# Shield_Eth06-REV3.net
KiCad netlist of a schematic drawn in EAGLE
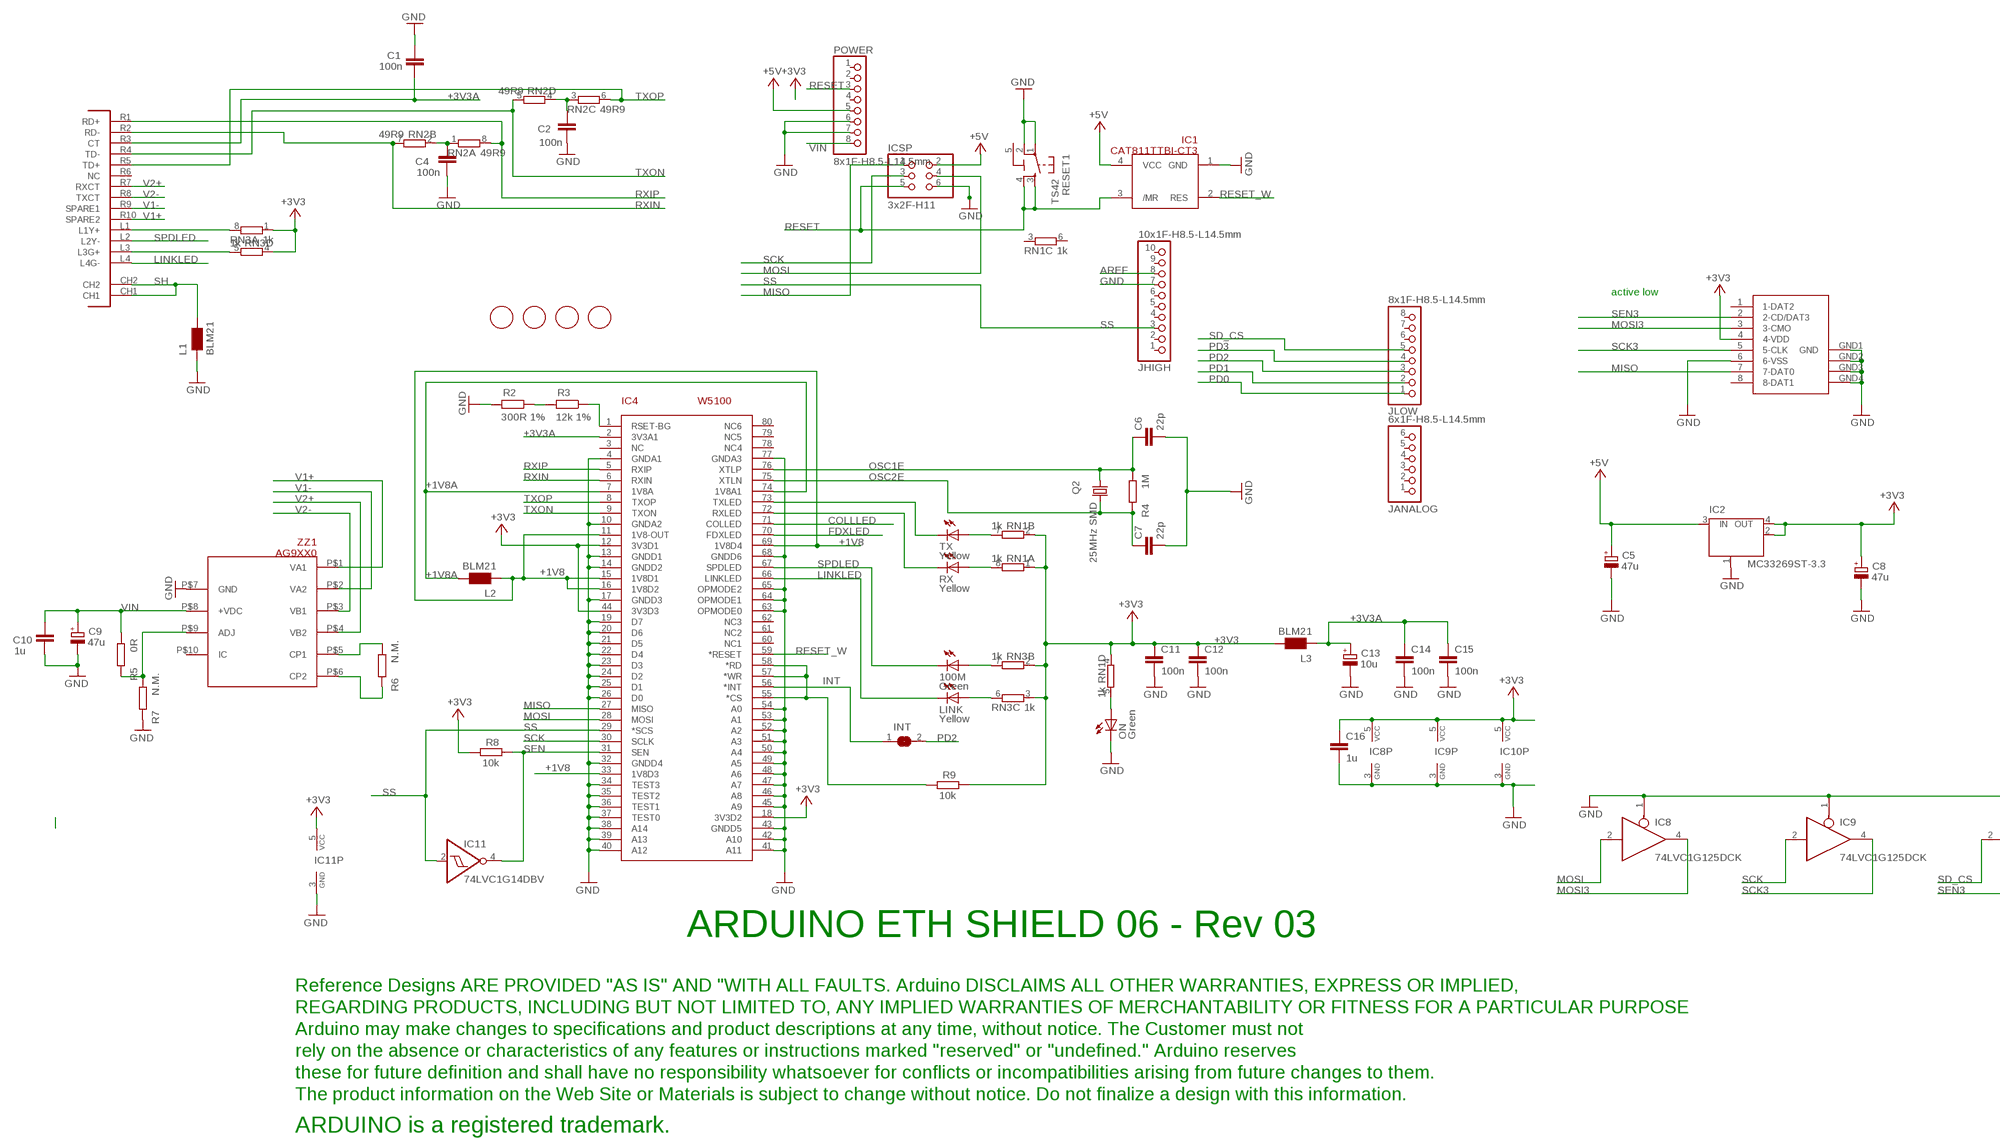
[diagram p0: schematic, sheet 1, part 1 of 2]
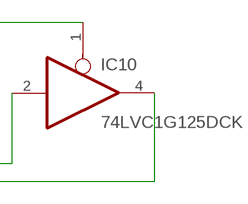
[diagram p1: schematic, sheet 1, part 2 of 2]

(export (version "E")
  (design (tool "Eeschema 10.0.6"))
  (components
    (comp (ref "100M")
      (value "Green")
      (footprint "eagle-import:CHIPLED_0805")
      (libsource (lib "eagle-import") (part "LEDCHIPLED_0805"))
    )
    (comp (ref "C1")
      (value "100n")
      (footprint "eagle-import:C0603-ROUND")
      (libsource (lib "eagle-import") (part "C-EUC0603"))
    )
    (comp (ref "C2")
      (value "100n")
      (footprint "eagle-import:C0603-ROUND")
      (libsource (lib "eagle-import") (part "C-EUC0603"))
    )
    (comp (ref "C4")
      (value "100n")
      (footprint "eagle-import:C0603-ROUND")
      (libsource (lib "eagle-import") (part "C-EUC0603"))
    )
    (comp (ref "C5")
      (value "47u")
      (footprint "eagle-import:PANASONIC_D")
      (libsource (lib "eagle-import") (part "CPOL-EUD"))
    )
    (comp (ref "C6")
      (value "22p")
      (footprint "eagle-import:C0603-ROUND")
      (libsource (lib "eagle-import") (part "C-EUC0603"))
    )
    (comp (ref "C7")
      (value "22p")
      (footprint "eagle-import:C0603-ROUND")
      (libsource (lib "eagle-import") (part "C-EUC0603"))
    )
    (comp (ref "C8")
      (value "47u")
      (footprint "eagle-import:PANASONIC_D")
      (libsource (lib "eagle-import") (part "CPOL-EUD"))
    )
    (comp (ref "C9")
      (value "47u")
      (footprint "eagle-import:PANASONIC_D")
      (libsource (lib "eagle-import") (part "CPOL-EUD"))
    )
    (comp (ref "C10")
      (value "1u")
      (footprint "eagle-import:C0603-ROUND")
      (libsource (lib "eagle-import") (part "C-EUC0603"))
    )
    (comp (ref "C11")
      (value "100n")
      (footprint "eagle-import:C0603-ROUND")
      (libsource (lib "eagle-import") (part "C-EUC0603"))
    )
    (comp (ref "C12")
      (value "100n")
      (footprint "eagle-import:C0603-ROUND")
      (libsource (lib "eagle-import") (part "C-EUC0603"))
    )
    (comp (ref "C13")
      (value "10u")
      (footprint "eagle-import:SMC_B")
      (libsource (lib "eagle-import") (part "CPOL-EUSMCB"))
    )
    (comp (ref "C14")
      (value "100n")
      (footprint "eagle-import:C0603-ROUND")
      (libsource (lib "eagle-import") (part "C-EUC0603"))
    )
    (comp (ref "C15")
      (value "100n")
      (footprint "eagle-import:C0603-ROUND")
      (libsource (lib "eagle-import") (part "C-EUC0603"))
    )
    (comp (ref "C16")
      (value "1u")
      (footprint "eagle-import:C0603-ROUND")
      (libsource (lib "eagle-import") (part "C-EUC0603"))
    )
    (comp (ref "FID1")
      (value "FIDUCIALMOUNT")
      (footprint "eagle-import:FIDUCIA-MOUNT")
      (libsource (lib "eagle-import") (part "FIDUCIALMOUNT"))
    )
    (comp (ref "FID2")
      (value "FIDUCIALMOUNT")
      (footprint "eagle-import:FIDUCIA-MOUNT")
      (libsource (lib "eagle-import") (part "FIDUCIALMOUNT"))
    )
    (comp (ref "FID3")
      (value "FIDUCIALMOUNT")
      (footprint "eagle-import:FIDUCIA-MOUNT")
      (libsource (lib "eagle-import") (part "FIDUCIALMOUNT"))
    )
    (comp (ref "FID4")
      (value "FIDUCIALMOUNT")
      (footprint "eagle-import:FIDUCIA-MOUNT")
      (libsource (lib "eagle-import") (part "FIDUCIALMOUNT"))
    )
    (comp (ref "IC1")
      (value "CAT811TTBI-CT3")
      (footprint "eagle-import:SOT143")
      (libsource (lib "eagle-import") (part "STM812"))
    )
    (comp (ref "IC2")
      (value "MC33269ST-3.3")
      (footprint "eagle-import:SOT223")
      (libsource (lib "eagle-import") (part "MC33269ST-3.3T3"))
    )
    (comp (ref "IC4")
      (value "W5100")
      (footprint "eagle-import:SQFP-S-10X10-80")
      (libsource (lib "eagle-import") (part "W5100"))
    )
    (comp (ref "IC8")
      (value "74LVC1G125DCK")
      (footprint "eagle-import:SC70-5")
      (libsource (lib "eagle-import") (part "741G125DCKLVC"))
    )
    (comp (ref "IC9")
      (value "74LVC1G125DCK")
      (footprint "eagle-import:SC70-5")
      (libsource (lib "eagle-import") (part "741G125DCKLVC"))
    )
    (comp (ref "IC10")
      (value "74LVC1G125DCK")
      (footprint "eagle-import:SC70-5")
      (libsource (lib "eagle-import") (part "741G125DCKLVC"))
    )
    (comp (ref "IC11")
      (value "74LVC1G14DBV")
      (footprint "eagle-import:SOT23-5")
      (libsource (lib "eagle-import") (part "741G14DBVLVC"))
    )
    (comp (ref "ICSP")
      (value "3x2F-H11")
      (footprint "eagle-import:2X03")
      (libsource (lib "eagle-import") (part "PINHD-2X3"))
    )
    (comp (ref "INT") (value "SJ") (footprint "eagle-import:SJ") (libsource (lib "eagle-import") (part "SJ")))
    (comp (ref "JANALOG")
      (value "6x1F-H8.5-L14.5mm")
      (footprint "eagle-import:1X06")
      (libsource (lib "eagle-import") (part "PINHD-1X6"))
    )
    (comp (ref "JHIGH")
      (value "10x1F-H8.5-L14.5mm")
      (footprint "eagle-import:1X10")
      (libsource (lib "eagle-import") (part "PINHD-1X10"))
    )
    (comp (ref "JLOW")
      (value "8x1F-H8.5-L14.5mm")
      (footprint "eagle-import:1X08")
      (libsource (lib "eagle-import") (part "PINHD-1X8"))
    )
    (comp (ref "L1")
      (value "BLM21")
      (footprint "eagle-import:0805")
      (libsource (lib "eagle-import") (part "WE-CBF_0805"))
    )
    (comp (ref "L2")
      (value "BLM21")
      (footprint "eagle-import:0805")
      (libsource (lib "eagle-import") (part "WE-CBF_0805"))
    )
    (comp (ref "L3")
      (value "BLM21")
      (footprint "eagle-import:0805")
      (libsource (lib "eagle-import") (part "WE-CBF_0805"))
    )
    (comp (ref "LINK")
      (value "Yellow")
      (footprint "eagle-import:CHIPLED_0805")
      (libsource (lib "eagle-import") (part "LEDCHIPLED_0805"))
    )
    (comp (ref "ON")
      (value "Green")
      (footprint "eagle-import:CHIPLED_0805")
      (libsource (lib "eagle-import") (part "LEDCHIPLED_0805"))
    )
    (comp (ref "POWER")
      (value "8x1F-H8.5-L14.5mm")
      (footprint "eagle-import:1X08")
      (libsource (lib "eagle-import") (part "PINHD-1X8"))
    )
    (comp (ref "Q2")
      (value "25MHz SMD")
      (footprint "eagle-import:HC49UP")
      (libsource (lib "eagle-import") (part "CRYSTALHC49UP"))
    )
    (comp (ref "R2")
      (value "300R 1%")
      (footprint "eagle-import:R0603-ROUND")
      (libsource (lib "eagle-import") (part "R-EU_0603-RND"))
    )
    (comp (ref "R3")
      (value "12k 1%")
      (footprint "eagle-import:R0603-ROUND")
      (libsource (lib "eagle-import") (part "R-EU_0603-RND"))
    )
    (comp (ref "R4")
      (value "1M")
      (footprint "eagle-import:R0603-ROUND")
      (libsource (lib "eagle-import") (part "R-EU_0603-RND"))
    )
    (comp (ref "R5")
      (value "0R")
      (footprint "eagle-import:R0603-ROUND")
      (libsource (lib "eagle-import") (part "R-EU_0603-RND"))
    )
    (comp (ref "R6")
      (value "N.M.")
      (footprint "eagle-import:R0603-ROUND")
      (libsource (lib "eagle-import") (part "R-EU_0603-RND"))
    )
    (comp (ref "R7")
      (value "N.M.")
      (footprint "eagle-import:R0603-ROUND")
      (libsource (lib "eagle-import") (part "R-EU_0603-RND"))
    )
    (comp (ref "R8")
      (value "10k")
      (footprint "eagle-import:R0603-ROUND")
      (libsource (lib "eagle-import") (part "R-EU_0603-RND"))
    )
    (comp (ref "R9")
      (value "10k")
      (footprint "eagle-import:R0603-ROUND")
      (libsource (lib "eagle-import") (part "R-EU_R0603"))
    )
    (comp (ref "RESET1")
      (value "TS42")
      (footprint "eagle-import:TS42")
      (libsource (lib "eagle-import") (part "TS42"))
    )
    (comp (ref "RN1")
      (value "1k")
      (footprint "eagle-import:CAY16")
      (libsource (lib "eagle-import") (part "4R-NCAY16"))
    )
    (comp (ref "RN2")
      (value "49R9")
      (footprint "eagle-import:CAY16")
      (libsource (lib "eagle-import") (part "4R-NCAY16"))
    )
    (comp (ref "RN3")
      (value "1k")
      (footprint "eagle-import:CAY16")
      (libsource (lib "eagle-import") (part "4R-NCAY16"))
    )
    (comp (ref "RX")
      (value "Yellow")
      (footprint "eagle-import:CHIPLED_0805")
      (libsource (lib "eagle-import") (part "LEDCHIPLED_0805"))
    )
    (comp (ref "TX")
      (value "Yellow")
      (footprint "eagle-import:CHIPLED_0805")
      (libsource (lib "eagle-import") (part "LEDCHIPLED_0805"))
    )
    (comp (ref "U$1")
      (value "POE-RJ45")
      (footprint "eagle-import:POE-RJ45")
      (libsource (lib "eagle-import") (part "POE-RJ45"))
    )
    (comp (ref "U$2")
      (value "DISCLAIMER")
      (footprint "eagle-import:DISCLAIMER")
      (libsource (lib "eagle-import") (part "DISCLAIMER"))
    )
    (comp (ref "X1")
      (value "SDCARD-15TW-8821")
      (footprint "eagle-import:SDCARD-15TW-8821")
      (libsource (lib "eagle-import") (part "SDCARD-15TW-8821"))
    )
    (comp (ref "ZZ1")
      (value "AG9XX0")
      (footprint "eagle-import:AG9000")
      (libsource (lib "eagle-import") (part "AG9XX0"))
    )
  )
  (nets
    (net (code "1") (name "+3V3") (class "Default")
      (node (ref "C11") (pin "1") (pinfunction "1_1") (pintype "passive"))
      (node (ref "C12") (pin "1") (pinfunction "1_1") (pintype "passive"))
      (node (ref "C16") (pin "1") (pinfunction "1_1") (pintype "passive"))
      (node (ref "C8") (pin "+") (pinfunction "+_+") (pintype "passive"))
      (node (ref "IC10") (pin "5") (pinfunction "VCC_5") (pintype "power_in"))
      (node (ref "IC11") (pin "5") (pinfunction "VCC_5") (pintype "power_in"))
      (node (ref "IC2") (pin "2") (pinfunction "OUT_2") (pintype "passive"))
      (node (ref "IC2") (pin "4") (pinfunction "OUT_4") (pintype "passive"))
      (node (ref "IC4") (pin "12") (pinfunction "3V3D1_12") (pintype "power_in"))
      (node (ref "IC4") (pin "18") (pinfunction "3V3D2_18") (pintype "power_in"))
      (node (ref "IC4") (pin "44") (pinfunction "3V3D3_44") (pintype "power_in"))
      (node (ref "IC8") (pin "5") (pinfunction "VCC_5") (pintype "power_in"))
      (node (ref "IC9") (pin "5") (pinfunction "VCC_5") (pintype "power_in"))
      (node (ref "L3") (pin "2") (pinfunction "2_2") (pintype "passive"))
      (node (ref "R8") (pin "1") (pinfunction "1_1") (pintype "passive"))
      (node (ref "R9") (pin "2") (pinfunction "2_2") (pintype "passive"))
      (node (ref "RN1") (pin "1") (pinfunction "1_1") (pintype "passive"))
      (node (ref "RN1") (pin "2") (pinfunction "1_2") (pintype "passive"))
      (node (ref "RN1") (pin "4") (pinfunction "1_4") (pintype "passive"))
      (node (ref "RN3") (pin "1") (pinfunction "1_1") (pintype "passive"))
      (node (ref "RN3") (pin "2") (pinfunction "1_2") (pintype "passive"))
      (node (ref "RN3") (pin "3") (pinfunction "1_3") (pintype "passive"))
      (node (ref "RN3") (pin "4") (pinfunction "1_4") (pintype "passive"))
      (node (ref "X1") (pin "4") (pinfunction "4-VDD_4") (pintype "bidirectional"))
    )
    (net (code "2") (name "+5V") (class "Default")
      (node (ref "C5") (pin "+") (pinfunction "+_+") (pintype "passive"))
      (node (ref "IC1") (pin "4") (pinfunction "VCC_4") (pintype "power_in"))
      (node (ref "IC2") (pin "3") (pinfunction "IN_3") (pintype "input"))
      (node (ref "ICSP") (pin "2") (pinfunction "2_2") (pintype "passive"))
      (node (ref "POWER") (pin "5") (pinfunction "5_5") (pintype "passive"))
    )
    (net (code "3") (name "/+1V8") (class "Default")
      (node (ref "IC4") (pin "11") (pinfunction "1V8-OUT_11") (pintype "power_in"))
      (node (ref "IC4") (pin "15") (pinfunction "1V8D1_15") (pintype "power_in"))
      (node (ref "IC4") (pin "16") (pinfunction "1V8D2_16") (pintype "power_in"))
      (node (ref "IC4") (pin "33") (pinfunction "1V8D3_33") (pintype "power_in"))
      (node (ref "IC4") (pin "69") (pinfunction "1V8D4_69") (pintype "power_in"))
      (node (ref "L2") (pin "1") (pinfunction "1_1") (pintype "passive"))
    )
    (net (code "4") (name "/+1V8A") (class "Default")
      (node (ref "IC4") (pin "7") (pinfunction "1V8A_7") (pintype "power_in"))
      (node (ref "IC4") (pin "74") (pinfunction "1V8A1_74") (pintype "power_in"))
      (node (ref "L2") (pin "2") (pinfunction "2_2") (pintype "passive"))
    )
    (net (code "5") (name "/+3V3A") (class "Default")
      (node (ref "C1") (pin "1") (pinfunction "1_1") (pintype "passive"))
      (node (ref "C13") (pin "+") (pinfunction "+_+") (pintype "passive"))
      (node (ref "C14") (pin "1") (pinfunction "1_1") (pintype "passive"))
      (node (ref "C15") (pin "1") (pinfunction "1_1") (pintype "passive"))
      (node (ref "IC4") (pin "2") (pinfunction "3V3A1_2") (pintype "power_in"))
      (node (ref "L3") (pin "1") (pinfunction "1_1") (pintype "passive"))
      (node (ref "U$1") (pin "R3") (pinfunction "CT_R3") (pintype "bidirectional"))
    )
    (net (code "6") (name "/5-GND") (class "Default")
      (node (ref "RESET1") (pin "5") (pinfunction "5-GND_5") (pintype "power_in"))
    )
    (net (code "7") (name "/AREF") (class "Default")
      (node (ref "JHIGH") (pin "8") (pinfunction "8_8") (pintype "passive"))
    )
    (net (code "8") (name "/COLLLED") (class "Default")
      (node (ref "IC4") (pin "71") (pinfunction "COLLED_71") (pintype "output"))
    )
    (net (code "9") (name "/FDXLED") (class "Default")
      (node (ref "IC4") (pin "70") (pinfunction "FDXLED_70") (pintype "output"))
    )
    (net (code "10") (name "/INT") (class "Default")
      (node (ref "IC4") (pin "56") (pinfunction "*INT_56") (pintype "input"))
      (node (ref "INT") (pin "1") (pinfunction "1_1") (pintype "passive"))
    )
    (net (code "11") (name "/LINKLED") (class "Default")
      (node (ref "IC4") (pin "66") (pinfunction "LINKLED_66") (pintype "output"))
      (node (ref "LINK") (pin "C") (pinfunction "C_C") (pintype "passive"))
      (node (ref "U$1") (pin "L4") (pinfunction "L4G-_L4") (pintype "bidirectional"))
    )
    (net (code "12") (name "/MISO") (class "Default")
      (node (ref "IC4") (pin "27") (pinfunction "MISO_27") (pintype "input"))
      (node (ref "ICSP") (pin "1") (pinfunction "1_1") (pintype "passive"))
      (node (ref "X1") (pin "7") (pinfunction "7-DAT0_7") (pintype "bidirectional"))
    )
    (net (code "13") (name "/MOSI") (class "Default")
      (node (ref "IC4") (pin "28") (pinfunction "MOSI_28") (pintype "output"))
      (node (ref "IC8") (pin "2") (pinfunction "I_2") (pintype "input"))
      (node (ref "ICSP") (pin "4") (pinfunction "4_4") (pintype "passive"))
    )
    (net (code "14") (name "/MOSI3") (class "Default")
      (node (ref "IC8") (pin "4") (pinfunction "O_4") (pintype "tri_state"))
      (node (ref "X1") (pin "3") (pinfunction "3-CMO_3") (pintype "bidirectional"))
    )
    (net (code "15") (name "/OSC1E") (class "Default")
      (node (ref "C6") (pin "1") (pinfunction "1_1") (pintype "passive"))
      (node (ref "IC4") (pin "76") (pinfunction "XTLP_76") (pintype "output"))
      (node (ref "Q2") (pin "1") (pinfunction "1_1") (pintype "passive"))
      (node (ref "R4") (pin "1") (pinfunction "1_1") (pintype "passive"))
    )
    (net (code "16") (name "/OSC2E") (class "Default")
      (node (ref "C7") (pin "1") (pinfunction "1_1") (pintype "passive"))
      (node (ref "IC4") (pin "75") (pinfunction "XTLN_75") (pintype "output"))
      (node (ref "Q2") (pin "2") (pinfunction "2_2") (pintype "passive"))
      (node (ref "R4") (pin "2") (pinfunction "2_2") (pintype "passive"))
    )
    (net (code "17") (name "/PD0") (class "Default")
      (node (ref "JLOW") (pin "1") (pinfunction "1_1") (pintype "passive"))
    )
    (net (code "18") (name "/PD1") (class "Default")
      (node (ref "JLOW") (pin "2") (pinfunction "2_2") (pintype "passive"))
    )
    (net (code "19") (name "/PD2") (class "Default")
      (node (ref "INT") (pin "2") (pinfunction "2_2") (pintype "passive"))
      (node (ref "JLOW") (pin "3") (pinfunction "3_3") (pintype "passive"))
    )
    (net (code "20") (name "/PD3") (class "Default")
      (node (ref "JLOW") (pin "4") (pinfunction "4_4") (pintype "passive"))
    )
    (net (code "21") (name "/RESET") (class "Default")
      (node (ref "IC1") (pin "3") (pinfunction "/MR_3") (pintype "input"))
      (node (ref "ICSP") (pin "5") (pinfunction "5_5") (pintype "passive"))
      (node (ref "POWER") (pin "3") (pinfunction "3_3") (pintype "passive"))
      (node (ref "RESET1") (pin "3") (pinfunction "3_3") (pintype "passive"))
      (node (ref "RESET1") (pin "4") (pinfunction "4_4") (pintype "passive"))
    )
    (net (code "22") (name "/RESET_W") (class "Default")
      (node (ref "IC1") (pin "2") (pinfunction "RES_2") (pintype "output"))
      (node (ref "IC4") (pin "59") (pinfunction "*RESET_59") (pintype "input"))
    )
    (net (code "23") (name "/RXIN") (class "Default")
      (node (ref "IC4") (pin "6") (pinfunction "RXIN_6") (pintype "input"))
      (node (ref "RN2") (pin "7") (pinfunction "2_7") (pintype "passive"))
      (node (ref "U$1") (pin "R2") (pinfunction "RD-_R2") (pintype "bidirectional"))
    )
    (net (code "24") (name "/RXIP") (class "Default")
      (node (ref "IC4") (pin "5") (pinfunction "RXIP_5") (pintype "input"))
      (node (ref "RN2") (pin "8") (pinfunction "2_8") (pintype "passive"))
      (node (ref "U$1") (pin "R1") (pinfunction "RD+_R1") (pintype "bidirectional"))
    )
    (net (code "25") (name "/SCK") (class "Default")
      (node (ref "IC4") (pin "30") (pinfunction "SCLK_30") (pintype "input"))
      (node (ref "IC9") (pin "2") (pinfunction "I_2") (pintype "input"))
      (node (ref "ICSP") (pin "3") (pinfunction "3_3") (pintype "passive"))
    )
    (net (code "26") (name "/SCK3") (class "Default")
      (node (ref "IC9") (pin "4") (pinfunction "O_4") (pintype "tri_state"))
      (node (ref "X1") (pin "5") (pinfunction "5-CLK_5") (pintype "bidirectional"))
    )
    (net (code "27") (name "/SD_CS") (class "Default")
      (node (ref "IC10") (pin "2") (pinfunction "I_2") (pintype "input"))
      (node (ref "JLOW") (pin "5") (pinfunction "5_5") (pintype "passive"))
    )
    (net (code "28") (name "/SEN") (class "Default")
      (node (ref "IC11") (pin "4") (pinfunction "O_4") (pintype "output"))
      (node (ref "IC4") (pin "31") (pinfunction "SEN_31") (pintype "input"))
      (node (ref "R8") (pin "2") (pinfunction "2_2") (pintype "passive"))
    )
    (net (code "29") (name "/SEN3") (class "Default")
      (node (ref "IC10") (pin "4") (pinfunction "O_4") (pintype "tri_state"))
      (node (ref "X1") (pin "2") (pinfunction "2-CD/DAT3_2") (pintype "bidirectional"))
    )
    (net (code "30") (name "/SH") (class "Default")
      (node (ref "L1") (pin "2") (pinfunction "2_2") (pintype "passive"))
      (node (ref "U$1") (pin "CH1") (pinfunction "CH1_CH1") (pintype "bidirectional"))
      (node (ref "U$1") (pin "CH2") (pinfunction "CH2_CH2") (pintype "bidirectional"))
    )
    (net (code "31") (name "/SPDLED") (class "Default")
      (node (ref "100M") (pin "C") (pinfunction "C_C") (pintype "passive"))
      (node (ref "IC4") (pin "67") (pinfunction "SPDLED_67") (pintype "output"))
      (node (ref "U$1") (pin "L2") (pinfunction "L2Y-_L2") (pintype "bidirectional"))
    )
    (net (code "32") (name "/SS") (class "Default")
      (node (ref "IC11") (pin "2") (pinfunction "I_2") (pintype "input"))
      (node (ref "IC4") (pin "29") (pinfunction "*SCS_29") (pintype "input"))
      (node (ref "JHIGH") (pin "3") (pinfunction "3_3") (pintype "passive"))
    )
    (net (code "33") (name "/TXON") (class "Default")
      (node (ref "IC4") (pin "9") (pinfunction "TXON_9") (pintype "output"))
      (node (ref "RN2") (pin "5") (pinfunction "2_5") (pintype "passive"))
      (node (ref "U$1") (pin "R4") (pinfunction "TD-_R4") (pintype "bidirectional"))
    )
    (net (code "34") (name "/TXOP") (class "Default")
      (node (ref "IC4") (pin "8") (pinfunction "TXOP_8") (pintype "output"))
      (node (ref "RN2") (pin "6") (pinfunction "2_6") (pintype "passive"))
      (node (ref "U$1") (pin "R5") (pinfunction "TD+_R5") (pintype "bidirectional"))
    )
    (net (code "35") (name "/V1+") (class "Default")
      (node (ref "U$1") (pin "R10") (pinfunction "SPARE2_R10") (pintype "bidirectional"))
      (node (ref "ZZ1") (pin "P$1") (pinfunction "VA1_P$1") (pintype "input"))
    )
    (net (code "36") (name "/V1-") (class "Default")
      (node (ref "U$1") (pin "R9") (pinfunction "SPARE1_R9") (pintype "bidirectional"))
      (node (ref "ZZ1") (pin "P$2") (pinfunction "VA2_P$2") (pintype "input"))
    )
    (net (code "37") (name "/V2+") (class "Default")
      (node (ref "U$1") (pin "R7") (pinfunction "RXCT_R7") (pintype "bidirectional"))
      (node (ref "ZZ1") (pin "P$4") (pinfunction "VB2_P$4") (pintype "input"))
    )
    (net (code "38") (name "/V2-") (class "Default")
      (node (ref "U$1") (pin "R8") (pinfunction "TXCT_R8") (pintype "bidirectional"))
      (node (ref "ZZ1") (pin "P$3") (pinfunction "VB1_P$3") (pintype "input"))
    )
    (net (code "39") (name "/VIN") (class "Default")
      (node (ref "C10") (pin "2") (pinfunction "2_2") (pintype "passive"))
      (node (ref "C9") (pin "+") (pinfunction "+_+") (pintype "passive"))
      (node (ref "POWER") (pin "8") (pinfunction "8_8") (pintype "passive"))
      (node (ref "R5") (pin "1") (pinfunction "1_1") (pintype "passive"))
      (node (ref "ZZ1") (pin "P$8") (pinfunction "+VDC_P$8") (pintype "power_in"))
    )
    (net (code "40") (name "GND") (class "Default")
      (node (ref "C1") (pin "2") (pinfunction "2_2") (pintype "passive"))
      (node (ref "C10") (pin "1") (pinfunction "1_1") (pintype "passive"))
      (node (ref "C11") (pin "2") (pinfunction "2_2") (pintype "passive"))
      (node (ref "C12") (pin "2") (pinfunction "2_2") (pintype "passive"))
      (node (ref "C13") (pin "-") (pinfunction "-_-") (pintype "passive"))
      (node (ref "C14") (pin "2") (pinfunction "2_2") (pintype "passive"))
      (node (ref "C15") (pin "2") (pinfunction "2_2") (pintype "passive"))
      (node (ref "C16") (pin "2") (pinfunction "2_2") (pintype "passive"))
      (node (ref "C2") (pin "1") (pinfunction "1_1") (pintype "passive"))
      (node (ref "C4") (pin "1") (pinfunction "1_1") (pintype "passive"))
      (node (ref "C5") (pin "-") (pinfunction "-_-") (pintype "passive"))
      (node (ref "C6") (pin "2") (pinfunction "2_2") (pintype "passive"))
      (node (ref "C7") (pin "2") (pinfunction "2_2") (pintype "passive"))
      (node (ref "C8") (pin "-") (pinfunction "-_-") (pintype "passive"))
      (node (ref "C9") (pin "-") (pinfunction "-_-") (pintype "passive"))
      (node (ref "IC1") (pin "1") (pinfunction "GND_1") (pintype "power_in"))
      (node (ref "IC10") (pin "1") (pinfunction "OE_1") (pintype "input"))
      (node (ref "IC10") (pin "3") (pinfunction "GND_3") (pintype "power_in"))
      (node (ref "IC11") (pin "3") (pinfunction "GND_3") (pintype "power_in"))
      (node (ref "IC2") (pin "1") (pinfunction "GND/ADJ_1") (pintype "input"))
      (node (ref "IC4") (pin "10") (pinfunction "GNDA2_10") (pintype "power_in"))
      (node (ref "IC4") (pin "13") (pinfunction "GNDD1_13") (pintype "power_in"))
      (node (ref "IC4") (pin "14") (pinfunction "GNDD2_14") (pintype "power_in"))
      (node (ref "IC4") (pin "17") (pinfunction "GNDD3_17") (pintype "power_in"))
      (node (ref "IC4") (pin "19") (pinfunction "D7_19") (pintype "input"))
      (node (ref "IC4") (pin "20") (pinfunction "D6_20") (pintype "input"))
      (node (ref "IC4") (pin "21") (pinfunction "D5_21") (pintype "input"))
      (node (ref "IC4") (pin "22") (pinfunction "D4_22") (pintype "input"))
      (node (ref "IC4") (pin "23") (pinfunction "D3_23") (pintype "input"))
      (node (ref "IC4") (pin "24") (pinfunction "D2_24") (pintype "input"))
      (node (ref "IC4") (pin "25") (pinfunction "D1_25") (pintype "input"))
      (node (ref "IC4") (pin "26") (pinfunction "D0_26") (pintype "input"))
      (node (ref "IC4") (pin "32") (pinfunction "GNDD4_32") (pintype "power_in"))
      (node (ref "IC4") (pin "34") (pinfunction "TEST3_34") (pintype "input"))
      (node (ref "IC4") (pin "35") (pinfunction "TEST2_35") (pintype "input"))
      (node (ref "IC4") (pin "36") (pinfunction "TEST1_36") (pintype "input"))
      (node (ref "IC4") (pin "37") (pinfunction "TEST0_37") (pintype "input"))
      (node (ref "IC4") (pin "38") (pinfunction "A14_38") (pintype "input"))
      (node (ref "IC4") (pin "39") (pinfunction "A13_39") (pintype "input"))
      (node (ref "IC4") (pin "4") (pinfunction "GNDA1_4") (pintype "power_in"))
      (node (ref "IC4") (pin "40") (pinfunction "A12_40") (pintype "input"))
      (node (ref "IC4") (pin "41") (pinfunction "A11_41") (pintype "input"))
      (node (ref "IC4") (pin "42") (pinfunction "A10_42") (pintype "input"))
      (node (ref "IC4") (pin "43") (pinfunction "GNDD5_43") (pintype "power_in"))
      (node (ref "IC4") (pin "45") (pinfunction "A9_45") (pintype "input"))
      (node (ref "IC4") (pin "46") (pinfunction "A8_46") (pintype "input"))
      (node (ref "IC4") (pin "47") (pinfunction "A7_47") (pintype "input"))
      (node (ref "IC4") (pin "48") (pinfunction "A6_48") (pintype "input"))
      (node (ref "IC4") (pin "49") (pinfunction "A5_49") (pintype "input"))
      (node (ref "IC4") (pin "50") (pinfunction "A4_50") (pintype "input"))
      (node (ref "IC4") (pin "51") (pinfunction "A3_51") (pintype "input"))
      (node (ref "IC4") (pin "52") (pinfunction "A2_52") (pintype "input"))
      (node (ref "IC4") (pin "53") (pinfunction "A1_53") (pintype "input"))
      (node (ref "IC4") (pin "54") (pinfunction "A0_54") (pintype "input"))
      (node (ref "IC4") (pin "63") (pinfunction "OPMODE0_63") (pintype "input"))
      (node (ref "IC4") (pin "64") (pinfunction "OPMODE1_64") (pintype "input"))
      (node (ref "IC4") (pin "65") (pinfunction "OPMODE2_65") (pintype "input"))
      (node (ref "IC4") (pin "68") (pinfunction "GNDD6_68") (pintype "power_in"))
      (node (ref "IC4") (pin "77") (pinfunction "GNDA3_77") (pintype "power_in"))
      (node (ref "IC8") (pin "1") (pinfunction "OE_1") (pintype "input"))
      (node (ref "IC8") (pin "3") (pinfunction "GND_3") (pintype "power_in"))
      (node (ref "IC9") (pin "1") (pinfunction "OE_1") (pintype "input"))
      (node (ref "IC9") (pin "3") (pinfunction "GND_3") (pintype "power_in"))
      (node (ref "ICSP") (pin "6") (pinfunction "6_6") (pintype "passive"))
      (node (ref "JHIGH") (pin "7") (pinfunction "7_7") (pintype "passive"))
      (node (ref "L1") (pin "1") (pinfunction "1_1") (pintype "passive"))
      (node (ref "ON") (pin "C") (pinfunction "C_C") (pintype "passive"))
      (node (ref "POWER") (pin "6") (pinfunction "6_6") (pintype "passive"))
      (node (ref "POWER") (pin "7") (pinfunction "7_7") (pintype "passive"))
      (node (ref "R2") (pin "2") (pinfunction "2_2") (pintype "passive"))
      (node (ref "R7") (pin "2") (pinfunction "2_2") (pintype "passive"))
      (node (ref "RESET1") (pin "1") (pinfunction "1_1") (pintype "passive"))
      (node (ref "RESET1") (pin "2") (pinfunction "2_2") (pintype "passive"))
      (node (ref "X1") (pin "6") (pinfunction "6-VSS_6") (pintype "bidirectional"))
      (node (ref "X1") (pin "GND1") (pinfunction "GND_GND1") (pintype "power_in"))
      (node (ref "X1") (pin "GND2") (pinfunction "GND1_GND2") (pintype "power_in"))
      (node (ref "X1") (pin "GND3") (pinfunction "GND2_GND3") (pintype "power_in"))
      (node (ref "X1") (pin "GND4") (pinfunction "GND3_GND4") (pintype "power_in"))
      (node (ref "ZZ1") (pin "P$7") (pinfunction "GND_P$7") (pintype "power_in"))
    )
    (net (code "41") (name "Net-(IC4-*CS)") (class "Default")
      (node (ref "IC4") (pin "55") (pinfunction "*CS_55") (pintype "input"))
      (node (ref "IC4") (pin "57") (pinfunction "*WR_57") (pintype "input"))
      (node (ref "IC4") (pin "58") (pinfunction "*RD_58") (pintype "input"))
      (node (ref "R9") (pin "1") (pinfunction "1_1") (pintype "passive"))
    )
    (net (code "42") (name "Net-(IC4-RSET-BG)") (class "Default")
      (node (ref "IC4") (pin "1") (pinfunction "RSET-BG_1") (pintype "input"))
      (node (ref "R3") (pin "1") (pinfunction "1_1") (pintype "passive"))
    )
    (net (code "43") (name "Net-(IC4-RXLED)") (class "Default")
      (node (ref "IC4") (pin "72") (pinfunction "RXLED_72") (pintype "output"))
      (node (ref "RX") (pin "C") (pinfunction "C_C") (pintype "passive"))
    )
    (net (code "44") (name "Net-(IC4-TXLED)") (class "Default")
      (node (ref "IC4") (pin "73") (pinfunction "TXLED_73") (pintype "output"))
      (node (ref "TX") (pin "C") (pinfunction "C_C") (pintype "passive"))
    )
    (net (code "45") (name "Net-(R2-Pad1)") (class "Default")
      (node (ref "R2") (pin "1") (pinfunction "1_1") (pintype "passive"))
      (node (ref "R3") (pin "2") (pinfunction "2_2") (pintype "passive"))
    )
    (net (code "46") (name "Net-(RN1A-2)") (class "Default")
      (node (ref "RN1") (pin "8") (pinfunction "2_8") (pintype "passive"))
      (node (ref "RX") (pin "A") (pinfunction "A_A") (pintype "passive"))
    )
    (net (code "47") (name "Net-(RN1B-2)") (class "Default")
      (node (ref "RN1") (pin "7") (pinfunction "2_7") (pintype "passive"))
      (node (ref "TX") (pin "A") (pinfunction "A_A") (pintype "passive"))
    )
    (net (code "48") (name "Net-(RN1D-2)") (class "Default")
      (node (ref "ON") (pin "A") (pinfunction "A_A") (pintype "passive"))
      (node (ref "RN1") (pin "5") (pinfunction "2_5") (pintype "passive"))
    )
    (net (code "49") (name "Net-(RN2B-1)") (class "Default")
      (node (ref "C4") (pin "2") (pinfunction "2_2") (pintype "passive"))
      (node (ref "RN2") (pin "1") (pinfunction "1_1") (pintype "passive"))
      (node (ref "RN2") (pin "2") (pinfunction "1_2") (pintype "passive"))
    )
    (net (code "50") (name "Net-(RN2C-1)") (class "Default")
      (node (ref "C2") (pin "2") (pinfunction "2_2") (pintype "passive"))
      (node (ref "RN2") (pin "3") (pinfunction "1_3") (pintype "passive"))
      (node (ref "RN2") (pin "4") (pinfunction "1_4") (pintype "passive"))
    )
    (net (code "51") (name "Net-(RN3A-2)") (class "Default")
      (node (ref "RN3") (pin "8") (pinfunction "2_8") (pintype "passive"))
      (node (ref "U$1") (pin "L1") (pinfunction "L1Y+_L1") (pintype "bidirectional"))
    )
    (net (code "52") (name "Net-(RN3B-2)") (class "Default")
      (node (ref "100M") (pin "A") (pinfunction "A_A") (pintype "passive"))
      (node (ref "RN3") (pin "7") (pinfunction "2_7") (pintype "passive"))
    )
    (net (code "53") (name "Net-(RN3C-2)") (class "Default")
      (node (ref "LINK") (pin "A") (pinfunction "A_A") (pintype "passive"))
      (node (ref "RN3") (pin "6") (pinfunction "2_6") (pintype "passive"))
    )
    (net (code "54") (name "Net-(RN3D-2)") (class "Default")
      (node (ref "RN3") (pin "5") (pinfunction "2_5") (pintype "passive"))
      (node (ref "U$1") (pin "L3") (pinfunction "L3G+_L3") (pintype "bidirectional"))
    )
    (net (code "55") (name "Net-(ZZ1-ADJ)") (class "Default")
      (node (ref "R5") (pin "2") (pinfunction "2_2") (pintype "passive"))
      (node (ref "R7") (pin "1") (pinfunction "1_1") (pintype "passive"))
      (node (ref "ZZ1") (pin "P$9") (pinfunction "ADJ_P$9") (pintype "passive"))
    )
    (net (code "56") (name "Net-(ZZ1-CP1)") (class "Default")
      (node (ref "R6") (pin "1") (pinfunction "1_1") (pintype "passive"))
      (node (ref "ZZ1") (pin "P$5") (pinfunction "CP1_P$5") (pintype "input"))
    )
    (net (code "57") (name "Net-(ZZ1-CP2)") (class "Default")
      (node (ref "R6") (pin "2") (pinfunction "2_2") (pintype "passive"))
      (node (ref "ZZ1") (pin "P$6") (pinfunction "CP2_P$6") (pintype "input"))
    )
    (net (code "58") (name "unconnected-(IC4-NC-Pad3)") (class "Default")
      (node (ref "IC4") (pin "3") (pinfunction "NC_3") (pintype "no_connect"))
    )
    (net (code "59") (name "unconnected-(IC4-NC1-Pad60)") (class "Default")
      (node (ref "IC4") (pin "60") (pinfunction "NC1_60") (pintype "no_connect"))
    )
    (net (code "60") (name "unconnected-(IC4-NC2-Pad61)") (class "Default")
      (node (ref "IC4") (pin "61") (pinfunction "NC2_61") (pintype "no_connect"))
    )
    (net (code "61") (name "unconnected-(IC4-NC3-Pad62)") (class "Default")
      (node (ref "IC4") (pin "62") (pinfunction "NC3_62") (pintype "no_connect"))
    )
    (net (code "62") (name "unconnected-(IC4-NC4-Pad78)") (class "Default")
      (node (ref "IC4") (pin "78") (pinfunction "NC4_78") (pintype "no_connect"))
    )
    (net (code "63") (name "unconnected-(IC4-NC5-Pad79)") (class "Default")
      (node (ref "IC4") (pin "79") (pinfunction "NC5_79") (pintype "no_connect"))
    )
    (net (code "64") (name "unconnected-(IC4-NC6-Pad80)") (class "Default")
      (node (ref "IC4") (pin "80") (pinfunction "NC6_80") (pintype "no_connect"))
    )
    (net (code "65") (name "unconnected-(JANALOG-Pad1)") (class "Default")
      (node (ref "JANALOG") (pin "1") (pinfunction "1_1") (pintype "passive"))
    )
    (net (code "66") (name "unconnected-(JANALOG-Pad2)") (class "Default")
      (node (ref "JANALOG") (pin "2") (pinfunction "2_2") (pintype "passive"))
    )
    (net (code "67") (name "unconnected-(JANALOG-Pad3)") (class "Default")
      (node (ref "JANALOG") (pin "3") (pinfunction "3_3") (pintype "passive"))
    )
    (net (code "68") (name "unconnected-(JANALOG-Pad4)") (class "Default")
      (node (ref "JANALOG") (pin "4") (pinfunction "4_4") (pintype "passive"))
    )
    (net (code "69") (name "unconnected-(JANALOG-Pad5)") (class "Default")
      (node (ref "JANALOG") (pin "5") (pinfunction "5_5") (pintype "passive"))
    )
    (net (code "70") (name "unconnected-(JANALOG-Pad6)") (class "Default")
      (node (ref "JANALOG") (pin "6") (pinfunction "6_6") (pintype "passive"))
    )
    (net (code "71") (name "unconnected-(JHIGH-Pad1)") (class "Default")
      (node (ref "JHIGH") (pin "1") (pinfunction "1_1") (pintype "passive"))
    )
    (net (code "72") (name "unconnected-(JHIGH-Pad2)") (class "Default")
      (node (ref "JHIGH") (pin "2") (pinfunction "2_2") (pintype "passive"))
    )
    (net (code "73") (name "unconnected-(JHIGH-Pad4)") (class "Default")
      (node (ref "JHIGH") (pin "4") (pinfunction "4_4") (pintype "passive"))
    )
    (net (code "74") (name "unconnected-(JHIGH-Pad5)") (class "Default")
      (node (ref "JHIGH") (pin "5") (pinfunction "5_5") (pintype "passive"))
    )
    (net (code "75") (name "unconnected-(JHIGH-Pad6)") (class "Default")
      (node (ref "JHIGH") (pin "6") (pinfunction "6_6") (pintype "passive"))
    )
    (net (code "76") (name "unconnected-(JHIGH-Pad9)") (class "Default")
      (node (ref "JHIGH") (pin "9") (pinfunction "9_9") (pintype "passive"))
    )
    (net (code "77") (name "unconnected-(JHIGH-Pad10)") (class "Default")
      (node (ref "JHIGH") (pin "10") (pinfunction "10_10") (pintype "passive"))
    )
    (net (code "78") (name "unconnected-(JLOW-Pad6)") (class "Default")
      (node (ref "JLOW") (pin "6") (pinfunction "6_6") (pintype "passive"))
    )
    (net (code "79") (name "unconnected-(JLOW-Pad7)") (class "Default")
      (node (ref "JLOW") (pin "7") (pinfunction "7_7") (pintype "passive"))
    )
    (net (code "80") (name "unconnected-(JLOW-Pad8)") (class "Default")
      (node (ref "JLOW") (pin "8") (pinfunction "8_8") (pintype "passive"))
    )
    (net (code "81") (name "unconnected-(POWER-Pad1)") (class "Default")
      (node (ref "POWER") (pin "1") (pinfunction "1_1") (pintype "passive"))
    )
    (net (code "82") (name "unconnected-(POWER-Pad2)") (class "Default")
      (node (ref "POWER") (pin "2") (pinfunction "2_2") (pintype "passive"))
    )
    (net (code "83") (name "unconnected-(POWER-Pad4)") (class "Default")
      (node (ref "POWER") (pin "4") (pinfunction "4_4") (pintype "passive"))
    )
    (net (code "84") (name "unconnected-(RN1C-1-Pad3)") (class "Default")
      (node (ref "RN1") (pin "3") (pinfunction "1_3") (pintype "passive"))
    )
    (net (code "85") (name "unconnected-(RN1C-2-Pad6)") (class "Default")
      (node (ref "RN1") (pin "6") (pinfunction "2_6") (pintype "passive"))
    )
    (net (code "86") (name "unconnected-(U$1-NC-PadR6)") (class "Default")
      (node (ref "U$1") (pin "R6") (pinfunction "NC_R6") (pintype "bidirectional"))
    )
    (net (code "87") (name "unconnected-(X1-1-DAT2-Pad1)") (class "Default")
      (node (ref "X1") (pin "1") (pinfunction "1-DAT2_1") (pintype "bidirectional"))
    )
    (net (code "88") (name "unconnected-(X1-8-DAT1-Pad8)") (class "Default")
      (node (ref "X1") (pin "8") (pinfunction "8-DAT1_8") (pintype "bidirectional"))
    )
    (net (code "89") (name "unconnected-(ZZ1-IC-PadP$10)") (class "Default")
      (node (ref "ZZ1") (pin "P$10") (pinfunction "IC_P$10") (pintype "no_connect"))
    )
  )
)
